# ruido.net
KiCad netlist of a schematic drawn in EAGLE
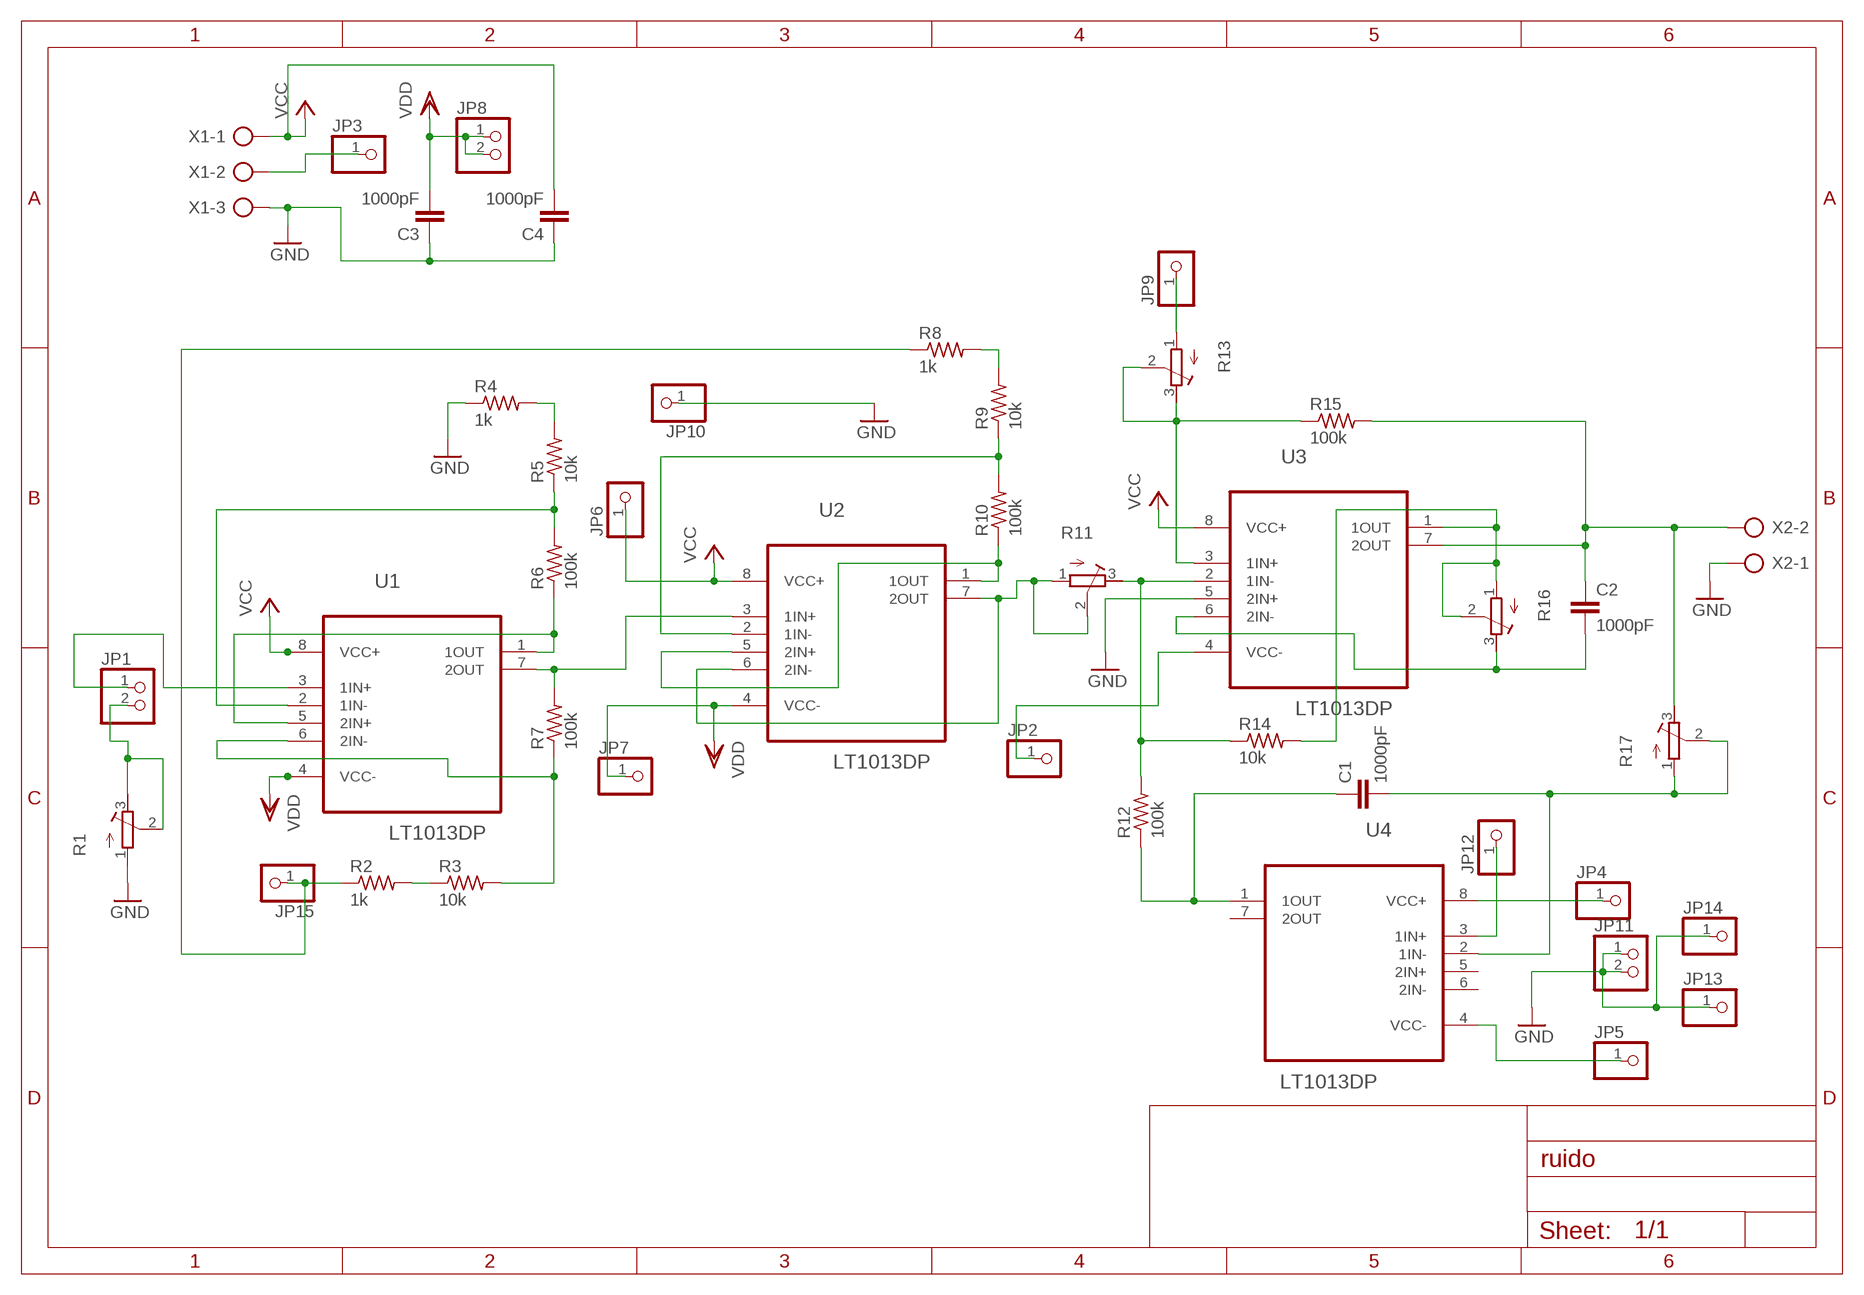
[diagram p0: schematic, sheet 1]

(export (version "E")
  (design (tool "Eeschema 10.0.6"))
  (components
    (comp (ref "C1")
      (value "1000pF")
      (footprint "eagle-import:C050-024X044")
      (libsource (lib "eagle-import") (part "C-EU050-024X044"))
    )
    (comp (ref "C2")
      (value "1000pF")
      (footprint "eagle-import:C050-024X044")
      (libsource (lib "eagle-import") (part "C-EU050-024X044"))
    )
    (comp (ref "C3")
      (value "1000pF")
      (footprint "eagle-import:C050-024X044")
      (libsource (lib "eagle-import") (part "C-EU050-024X044"))
    )
    (comp (ref "C4")
      (value "1000pF")
      (footprint "eagle-import:C050-024X044")
      (libsource (lib "eagle-import") (part "C-EU050-024X044"))
    )
    (comp (ref "JP1")
      (value "PINHD-1X2")
      (footprint "eagle-import:1X02")
      (libsource (lib "eagle-import") (part "PINHD-1X2"))
    )
    (comp (ref "JP2")
      (value "PINHD-1X1")
      (footprint "eagle-import:1X01")
      (libsource (lib "eagle-import") (part "PINHD-1X1"))
    )
    (comp (ref "JP3")
      (value "PINHD-1X1")
      (footprint "eagle-import:1X01")
      (libsource (lib "eagle-import") (part "PINHD-1X1"))
    )
    (comp (ref "JP4")
      (value "PINHD-1X1")
      (footprint "eagle-import:1X01")
      (libsource (lib "eagle-import") (part "PINHD-1X1"))
    )
    (comp (ref "JP5")
      (value "PINHD-1X1")
      (footprint "eagle-import:1X01")
      (libsource (lib "eagle-import") (part "PINHD-1X1"))
    )
    (comp (ref "JP6")
      (value "PINHD-1X1")
      (footprint "eagle-import:1X01")
      (libsource (lib "eagle-import") (part "PINHD-1X1"))
    )
    (comp (ref "JP7")
      (value "PINHD-1X1")
      (footprint "eagle-import:1X01")
      (libsource (lib "eagle-import") (part "PINHD-1X1"))
    )
    (comp (ref "JP8")
      (value "PINHD-1X2")
      (footprint "eagle-import:1X02")
      (libsource (lib "eagle-import") (part "PINHD-1X2"))
    )
    (comp (ref "JP9")
      (value "PINHD-1X1")
      (footprint "eagle-import:1X01")
      (libsource (lib "eagle-import") (part "PINHD-1X1"))
    )
    (comp (ref "JP10")
      (value "PINHD-1X1")
      (footprint "eagle-import:1X01")
      (libsource (lib "eagle-import") (part "PINHD-1X1"))
    )
    (comp (ref "JP11")
      (value "PINHD-1X2")
      (footprint "eagle-import:1X02")
      (libsource (lib "eagle-import") (part "PINHD-1X2"))
    )
    (comp (ref "JP12")
      (value "PINHD-1X1")
      (footprint "eagle-import:1X01")
      (libsource (lib "eagle-import") (part "PINHD-1X1"))
    )
    (comp (ref "JP13")
      (value "PINHD-1X1")
      (footprint "eagle-import:1X01")
      (libsource (lib "eagle-import") (part "PINHD-1X1"))
    )
    (comp (ref "JP14")
      (value "PINHD-1X1")
      (footprint "eagle-import:1X01")
      (libsource (lib "eagle-import") (part "PINHD-1X1"))
    )
    (comp (ref "JP15")
      (value "PINHD-1X1")
      (footprint "eagle-import:1X01")
      (libsource (lib "eagle-import") (part "PINHD-1X1"))
    )
    (comp (ref "R1")
      (value "R-TRIMM3296W")
      (footprint "eagle-import:RTRIM3296W")
      (libsource (lib "eagle-import") (part "R-TRIMM3296W"))
    )
    (comp (ref "R2")
      (value "1k")
      (footprint "eagle-import:0207_10")
      (libsource (lib "eagle-import") (part "R-US_0207/10"))
    )
    (comp (ref "R3")
      (value "10k")
      (footprint "eagle-import:0207_10")
      (libsource (lib "eagle-import") (part "R-US_0207/10"))
    )
    (comp (ref "R4")
      (value "1k")
      (footprint "eagle-import:0207_10")
      (libsource (lib "eagle-import") (part "R-US_0207/10"))
    )
    (comp (ref "R5")
      (value "10k")
      (footprint "eagle-import:0207_10")
      (libsource (lib "eagle-import") (part "R-US_0207/10"))
    )
    (comp (ref "R6")
      (value "100k")
      (footprint "eagle-import:0207_10")
      (fields (field (name "SPICEPREFIX") "100k"))
      (libsource (lib "eagle-import") (part "R-US_0207/10"))
    )
    (comp (ref "R7")
      (value "100k")
      (footprint "eagle-import:0207_10")
      (libsource (lib "eagle-import") (part "R-US_0207/10"))
    )
    (comp (ref "R8")
      (value "1k")
      (footprint "eagle-import:0207_10")
      (libsource (lib "eagle-import") (part "R-US_0207/10"))
    )
    (comp (ref "R9")
      (value "10k")
      (footprint "eagle-import:0207_10")
      (libsource (lib "eagle-import") (part "R-US_0207/10"))
    )
    (comp (ref "R10")
      (value "100k")
      (footprint "eagle-import:0207_10")
      (libsource (lib "eagle-import") (part "R-US_0207/10"))
    )
    (comp (ref "R11")
      (value "R-TRIMM3296W")
      (footprint "eagle-import:RTRIM3296W")
      (libsource (lib "eagle-import") (part "R-TRIMM3296W"))
    )
    (comp (ref "R12")
      (value "100k")
      (footprint "eagle-import:0207_10")
      (libsource (lib "eagle-import") (part "R-US_0207/10"))
    )
    (comp (ref "R13")
      (value "R-TRIMM3296W")
      (footprint "eagle-import:RTRIM3296W")
      (libsource (lib "eagle-import") (part "R-TRIMM3296W"))
    )
    (comp (ref "R14")
      (value "10k")
      (footprint "eagle-import:0207_10")
      (libsource (lib "eagle-import") (part "R-US_0207/10"))
    )
    (comp (ref "R15")
      (value "100k")
      (footprint "eagle-import:0207_10")
      (libsource (lib "eagle-import") (part "R-US_0207/10"))
    )
    (comp (ref "R16")
      (value "R-TRIMM3296W")
      (footprint "eagle-import:RTRIM3296W")
      (libsource (lib "eagle-import") (part "R-TRIMM3296W"))
    )
    (comp (ref "R17")
      (value "R-TRIMM3296W")
      (footprint "eagle-import:RTRIM3296W")
      (libsource (lib "eagle-import") (part "R-TRIMM3296W"))
    )
    (comp (ref "U1")
      (value "LT1013DP")
      (footprint "eagle-import:DIP254P762X508-8")
      (fields (field (name "MF") "Texas Instruments"))
      (libsource (lib "eagle-import") (part "LT1013DP"))
    )
    (comp (ref "U2")
      (value "LT1013DP")
      (footprint "eagle-import:DIP254P762X508-8")
      (fields (field (name "MF") "Texas Instruments"))
      (libsource (lib "eagle-import") (part "LT1013DP"))
    )
    (comp (ref "U3")
      (value "LT1013DP")
      (footprint "eagle-import:DIP254P762X508-8")
      (fields (field (name "MF") "Texas Instruments"))
      (libsource (lib "eagle-import") (part "LT1013DP"))
    )
    (comp (ref "U4")
      (value "LT1013DP")
      (footprint "eagle-import:DIP254P762X508-8")
      (fields (field (name "MF") "Texas Instruments"))
      (libsource (lib "eagle-import") (part "LT1013DP"))
    )
    (comp (ref "X1")
      (value "AK500/3")
      (footprint "eagle-import:AK500_3")
      (libsource (lib "eagle-import") (part "AK500/3"))
    )
    (comp (ref "X2")
      (value "AK500/2")
      (footprint "eagle-import:AK500_2")
      (libsource (lib "eagle-import") (part "AK500/2"))
    )
  )
  (nets
    (net (code "1") (name "GND") (class "Default")
      (node (ref "C3") (pin "1") (pinfunction "1_1") (pintype "passive"))
      (node (ref "C4") (pin "1") (pinfunction "1_1") (pintype "passive"))
      (node (ref "JP10") (pin "1") (pinfunction "1_1") (pintype "passive"))
      (node (ref "JP11") (pin "1") (pinfunction "1_1") (pintype "passive"))
      (node (ref "JP11") (pin "2") (pinfunction "2_2") (pintype "passive"))
      (node (ref "JP13") (pin "1") (pinfunction "1_1") (pintype "passive"))
      (node (ref "JP14") (pin "1") (pinfunction "1_1") (pintype "passive"))
      (node (ref "R1") (pin "1") (pinfunction "A_1") (pintype "passive"))
      (node (ref "R4") (pin "1") (pinfunction "1_1") (pintype "passive"))
      (node (ref "U3") (pin "5") (pinfunction "2IN+_5") (pintype "input"))
      (node (ref "X1") (pin "3") (pinfunction "KL_3") (pintype "passive"))
      (node (ref "X2") (pin "1") (pinfunction "KL_1") (pintype "passive"))
    )
    (net (code "2") (name "Net-(JP15-Pad1)") (class "Default")
      (node (ref "JP15") (pin "1") (pinfunction "1_1") (pintype "passive"))
      (node (ref "R2") (pin "1") (pinfunction "1_1") (pintype "passive"))
      (node (ref "R8") (pin "1") (pinfunction "1_1") (pintype "passive"))
    )
    (net (code "3") (name "Net-(R1-E)") (class "Default")
      (node (ref "JP1") (pin "2") (pinfunction "2_2") (pintype "passive"))
      (node (ref "R1") (pin "2") (pinfunction "S_2") (pintype "passive"))
      (node (ref "R1") (pin "3") (pinfunction "E_3") (pintype "passive"))
    )
    (net (code "4") (name "Net-(R2-Pad2)") (class "Default")
      (node (ref "R2") (pin "2") (pinfunction "2_2") (pintype "passive"))
      (node (ref "R3") (pin "1") (pinfunction "1_1") (pintype "passive"))
    )
    (net (code "5") (name "Net-(R4-Pad2)") (class "Default")
      (node (ref "R4") (pin "2") (pinfunction "2_2") (pintype "passive"))
      (node (ref "R5") (pin "2") (pinfunction "2_2") (pintype "passive"))
    )
    (net (code "6") (name "Net-(R8-Pad2)") (class "Default")
      (node (ref "R8") (pin "2") (pinfunction "2_2") (pintype "passive"))
      (node (ref "R9") (pin "2") (pinfunction "2_2") (pintype "passive"))
    )
    (net (code "7") (name "Net-(R11-A)") (class "Default")
      (node (ref "R11") (pin "1") (pinfunction "A_1") (pintype "passive"))
      (node (ref "R11") (pin "2") (pinfunction "S_2") (pintype "passive"))
      (node (ref "U2") (pin "6") (pinfunction "2IN-_6") (pintype "input"))
      (node (ref "U2") (pin "7") (pinfunction "2OUT_7") (pintype "output"))
    )
    (net (code "8") (name "Net-(R11-E)") (class "Default")
      (node (ref "R11") (pin "3") (pinfunction "E_3") (pintype "passive"))
      (node (ref "R12") (pin "2") (pinfunction "2_2") (pintype "passive"))
      (node (ref "R14") (pin "1") (pinfunction "1_1") (pintype "passive"))
      (node (ref "U3") (pin "2") (pinfunction "1IN-_2") (pintype "input"))
    )
    (net (code "9") (name "Net-(R13-A)") (class "Default")
      (node (ref "JP9") (pin "1") (pinfunction "1_1") (pintype "passive"))
      (node (ref "R13") (pin "1") (pinfunction "A_1") (pintype "passive"))
    )
    (net (code "10") (name "Net-(R13-E)") (class "Default")
      (node (ref "R13") (pin "2") (pinfunction "S_2") (pintype "passive"))
      (node (ref "R13") (pin "3") (pinfunction "E_3") (pintype "passive"))
      (node (ref "R15") (pin "1") (pinfunction "1_1") (pintype "passive"))
      (node (ref "U3") (pin "3") (pinfunction "1IN+_3") (pintype "input"))
    )
    (net (code "11") (name "Net-(R16-A)") (class "Default")
      (node (ref "R14") (pin "2") (pinfunction "2_2") (pintype "passive"))
      (node (ref "R16") (pin "1") (pinfunction "A_1") (pintype "passive"))
      (node (ref "R16") (pin "2") (pinfunction "S_2") (pintype "passive"))
      (node (ref "U3") (pin "1") (pinfunction "1OUT_1") (pintype "output"))
    )
    (net (code "12") (name "Net-(R16-E)") (class "Default")
      (node (ref "C2") (pin "2") (pinfunction "2_2") (pintype "passive"))
      (node (ref "R16") (pin "3") (pinfunction "E_3") (pintype "passive"))
      (node (ref "U3") (pin "6") (pinfunction "2IN-_6") (pintype "input"))
    )
    (net (code "13") (name "Net-(R17-A)") (class "Default")
      (node (ref "C1") (pin "2") (pinfunction "2_2") (pintype "passive"))
      (node (ref "R17") (pin "1") (pinfunction "A_1") (pintype "passive"))
      (node (ref "R17") (pin "2") (pinfunction "S_2") (pintype "passive"))
      (node (ref "U4") (pin "2") (pinfunction "1IN-_2") (pintype "input"))
    )
    (net (code "14") (name "Net-(R17-E)") (class "Default")
      (node (ref "C2") (pin "1") (pinfunction "1_1") (pintype "passive"))
      (node (ref "R15") (pin "2") (pinfunction "2_2") (pintype "passive"))
      (node (ref "R17") (pin "3") (pinfunction "E_3") (pintype "passive"))
      (node (ref "U3") (pin "7") (pinfunction "2OUT_7") (pintype "output"))
      (node (ref "X2") (pin "2") (pinfunction "KL_2") (pintype "passive"))
    )
    (net (code "15") (name "Net-(U1-1IN+)") (class "Default")
      (node (ref "JP1") (pin "1") (pinfunction "1_1") (pintype "passive"))
      (node (ref "U1") (pin "3") (pinfunction "1IN+_3") (pintype "input"))
    )
    (net (code "16") (name "Net-(U1-1IN-)") (class "Default")
      (node (ref "R5") (pin "1") (pinfunction "1_1") (pintype "passive"))
      (node (ref "R6") (pin "2") (pinfunction "2_2") (pintype "passive"))
      (node (ref "U1") (pin "2") (pinfunction "1IN-_2") (pintype "input"))
    )
    (net (code "17") (name "Net-(U1-1OUT)") (class "Default")
      (node (ref "R6") (pin "1") (pinfunction "1_1") (pintype "passive"))
      (node (ref "U1") (pin "1") (pinfunction "1OUT_1") (pintype "output"))
      (node (ref "U1") (pin "5") (pinfunction "2IN+_5") (pintype "input"))
    )
    (net (code "18") (name "Net-(U1-2IN-)") (class "Default")
      (node (ref "R3") (pin "2") (pinfunction "2_2") (pintype "passive"))
      (node (ref "R7") (pin "1") (pinfunction "1_1") (pintype "passive"))
      (node (ref "U1") (pin "6") (pinfunction "2IN-_6") (pintype "input"))
    )
    (net (code "19") (name "Net-(U1-2OUT)") (class "Default")
      (node (ref "R7") (pin "2") (pinfunction "2_2") (pintype "passive"))
      (node (ref "U1") (pin "7") (pinfunction "2OUT_7") (pintype "output"))
      (node (ref "U2") (pin "3") (pinfunction "1IN+_3") (pintype "input"))
    )
    (net (code "20") (name "Net-(U2-1IN-)") (class "Default")
      (node (ref "R10") (pin "2") (pinfunction "2_2") (pintype "passive"))
      (node (ref "R9") (pin "1") (pinfunction "1_1") (pintype "passive"))
      (node (ref "U2") (pin "2") (pinfunction "1IN-_2") (pintype "input"))
    )
    (net (code "21") (name "Net-(U2-1OUT)") (class "Default")
      (node (ref "R10") (pin "1") (pinfunction "1_1") (pintype "passive"))
      (node (ref "U2") (pin "1") (pinfunction "1OUT_1") (pintype "output"))
      (node (ref "U2") (pin "5") (pinfunction "2IN+_5") (pintype "input"))
    )
    (net (code "22") (name "Net-(U3-VCC-)") (class "Default")
      (node (ref "JP2") (pin "1") (pinfunction "1_1") (pintype "passive"))
      (node (ref "U3") (pin "4") (pinfunction "VCC-_4") (pintype "power_in"))
    )
    (net (code "23") (name "Net-(U4-1IN+)") (class "Default")
      (node (ref "JP12") (pin "1") (pinfunction "1_1") (pintype "passive"))
      (node (ref "U4") (pin "3") (pinfunction "1IN+_3") (pintype "input"))
    )
    (net (code "24") (name "Net-(U4-1OUT)") (class "Default")
      (node (ref "C1") (pin "1") (pinfunction "1_1") (pintype "passive"))
      (node (ref "R12") (pin "1") (pinfunction "1_1") (pintype "passive"))
      (node (ref "U4") (pin "1") (pinfunction "1OUT_1") (pintype "output"))
    )
    (net (code "25") (name "Net-(U4-VCC+)") (class "Default")
      (node (ref "JP4") (pin "1") (pinfunction "1_1") (pintype "passive"))
      (node (ref "U4") (pin "8") (pinfunction "VCC+_8") (pintype "power_in"))
    )
    (net (code "26") (name "Net-(U4-VCC-)") (class "Default")
      (node (ref "JP5") (pin "1") (pinfunction "1_1") (pintype "passive"))
      (node (ref "U4") (pin "4") (pinfunction "VCC-_4") (pintype "power_in"))
    )
    (net (code "27") (name "Net-(X1B-KL)") (class "Default")
      (node (ref "JP3") (pin "1") (pinfunction "1_1") (pintype "passive"))
      (node (ref "X1") (pin "2") (pinfunction "KL_2") (pintype "passive"))
    )
    (net (code "28") (name "VCC") (class "Default")
      (node (ref "C4") (pin "2") (pinfunction "2_2") (pintype "passive"))
      (node (ref "JP6") (pin "1") (pinfunction "1_1") (pintype "passive"))
      (node (ref "U1") (pin "8") (pinfunction "VCC+_8") (pintype "power_in"))
      (node (ref "U2") (pin "8") (pinfunction "VCC+_8") (pintype "power_in"))
      (node (ref "U3") (pin "8") (pinfunction "VCC+_8") (pintype "power_in"))
      (node (ref "X1") (pin "1") (pinfunction "KL_1") (pintype "passive"))
    )
    (net (code "29") (name "VDD") (class "Default")
      (node (ref "C3") (pin "2") (pinfunction "2_2") (pintype "passive"))
      (node (ref "JP7") (pin "1") (pinfunction "1_1") (pintype "passive"))
      (node (ref "JP8") (pin "1") (pinfunction "1_1") (pintype "passive"))
      (node (ref "JP8") (pin "2") (pinfunction "2_2") (pintype "passive"))
      (node (ref "U1") (pin "4") (pinfunction "VCC-_4") (pintype "power_in"))
      (node (ref "U2") (pin "4") (pinfunction "VCC-_4") (pintype "power_in"))
    )
    (net (code "30") (name "unconnected-(U4-2IN+-Pad5)") (class "Default")
      (node (ref "U4") (pin "5") (pinfunction "2IN+_5") (pintype "input"))
    )
    (net (code "31") (name "unconnected-(U4-2IN--Pad6)") (class "Default")
      (node (ref "U4") (pin "6") (pinfunction "2IN-_6") (pintype "input"))
    )
    (net (code "32") (name "unconnected-(U4-2OUT-Pad7)") (class "Default")
      (node (ref "U4") (pin "7") (pinfunction "2OUT_7") (pintype "output"))
    )
  )
)
